# I2CPANEL.net
KiCad netlist of a schematic drawn in EAGLE
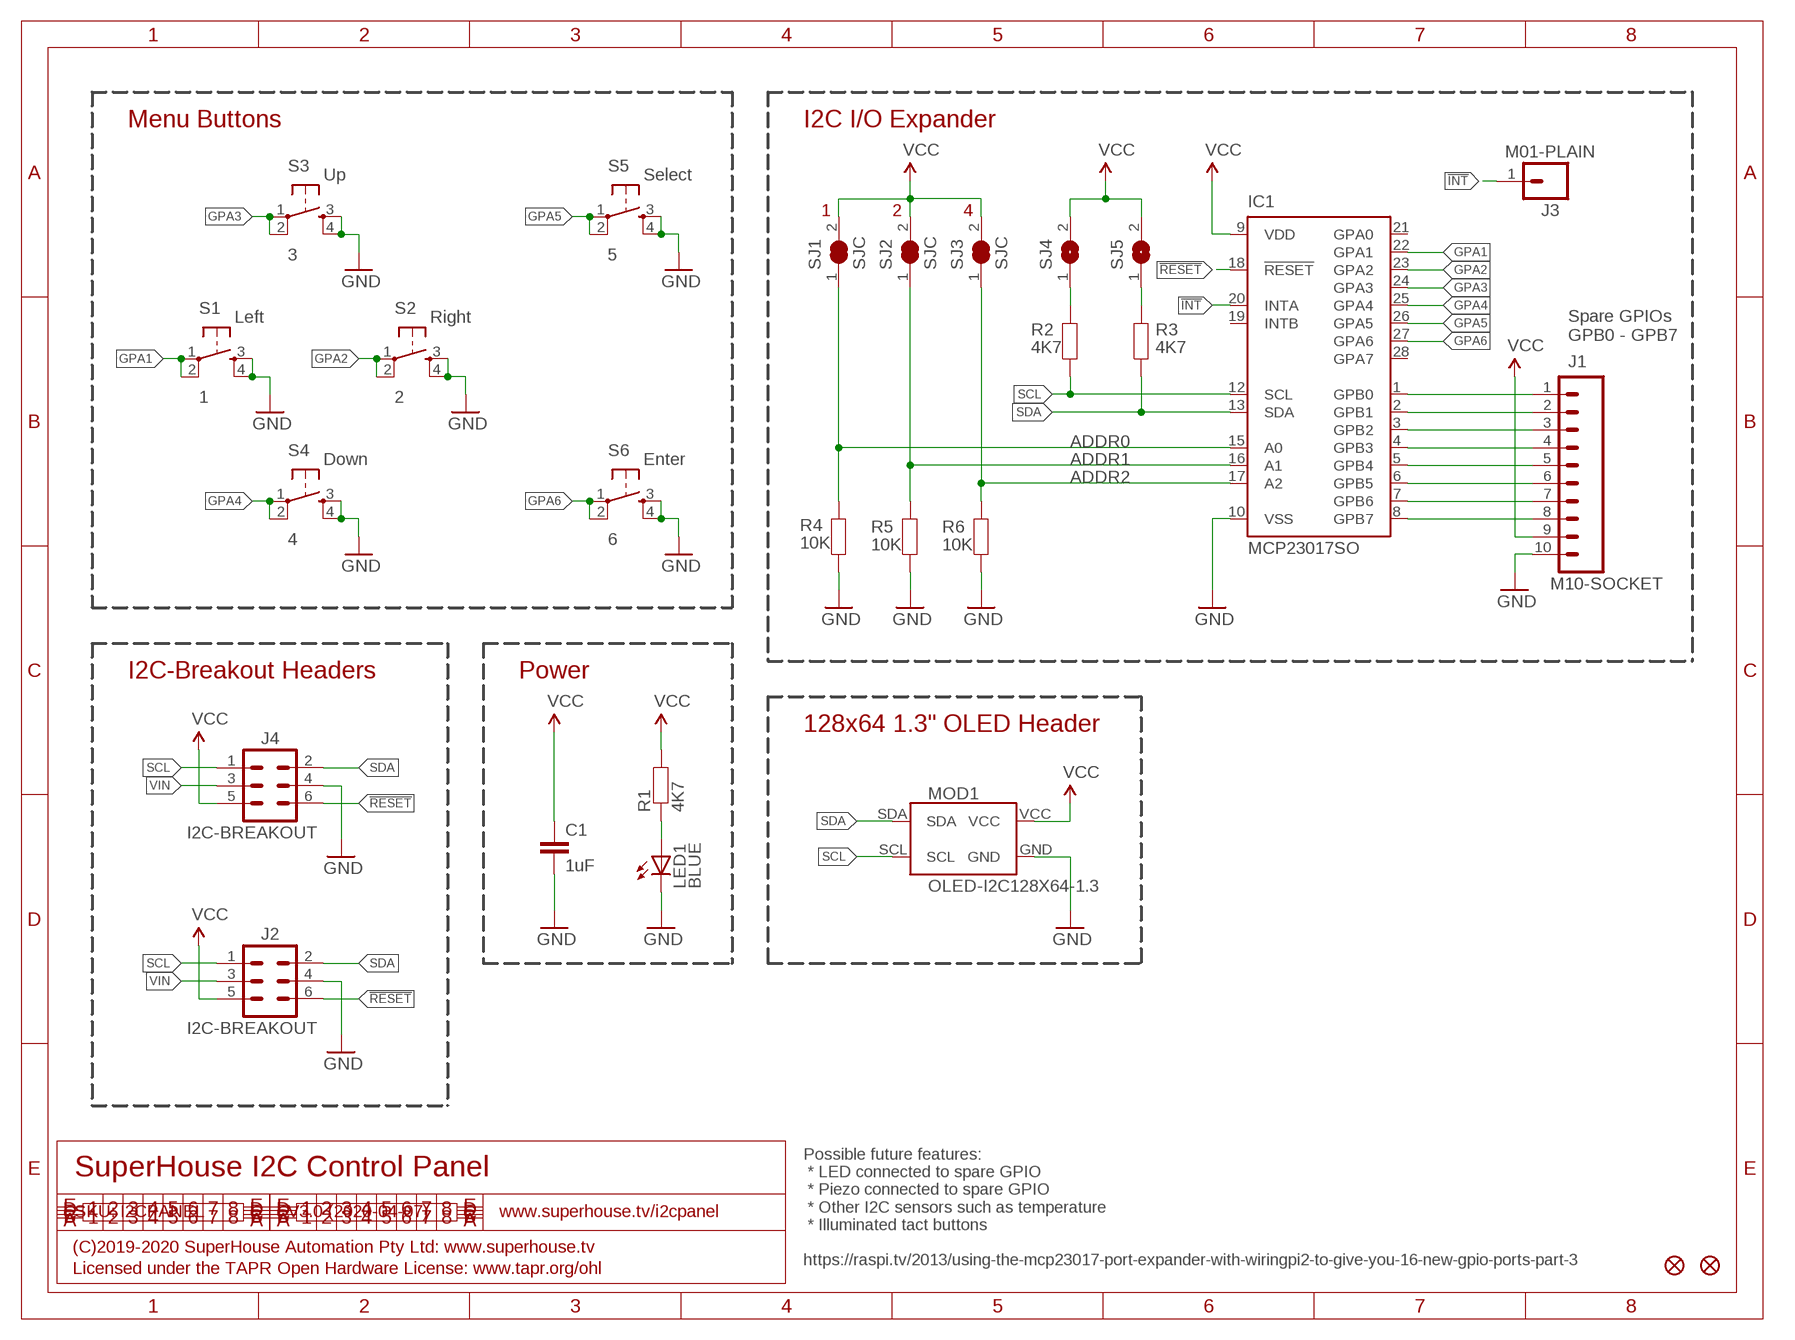
[diagram p0: schematic, sheet 1]

(export (version "E")
  (design (tool "Eeschema 10.0.6"))
  (components
    (comp (ref "C1")
      (value "1uF")
      (footprint "eagle-import:C0603")
      (libsource (lib "eagle-import") (part "CAP0603"))
    )
    (comp (ref "FID1")
      (value "FIDUCIAL1X2.5")
      (footprint "eagle-import:FIDUCIAL-1X2.5")
      (libsource (lib "eagle-import") (part "FIDUCIAL1X2.5"))
    )
    (comp (ref "FID2")
      (value "FIDUCIAL1X2.5")
      (footprint "eagle-import:FIDUCIAL-1X2.5")
      (libsource (lib "eagle-import") (part "FIDUCIAL1X2.5"))
    )
    (comp (ref "IC1")
      (value "MCP23017SO")
      (footprint "eagle-import:SO28W")
      (libsource (lib "eagle-import") (part "MCP23017SO"))
    )
    (comp (ref "J1")
      (value "M10-SOCKET")
      (footprint "eagle-import:1X10-S")
      (libsource (lib "eagle-import") (part "M10-SOCKET"))
    )
    (comp (ref "J2")
      (value "I2C-BREAKOUT")
      (footprint "eagle-import:2X03-SHROUDED")
      (libsource (lib "eagle-import") (part "M02X3-SHROUDED"))
    )
    (comp (ref "J3")
      (value "M01-PLAIN")
      (footprint "eagle-import:1X01")
      (libsource (lib "eagle-import") (part "M01-PLAIN"))
    )
    (comp (ref "J4")
      (value "I2C-BREAKOUT")
      (footprint "eagle-import:2X03-SHROUDED")
      (libsource (lib "eagle-import") (part "M02X3-SHROUDED"))
    )
    (comp (ref "LED1")
      (value "BLUE")
      (footprint "eagle-import:LED-0603")
      (libsource (lib "eagle-import") (part "LED0603"))
    )
    (comp (ref "MOD1")
      (value "OLED-I2C128X64-1.3")
      (footprint "eagle-import:OLED-128X64-1.3")
      (libsource (lib "eagle-import") (part "OLED-I2C128X64-1.3"))
    )
    (comp (ref "R1")
      (value "4K7")
      (footprint "eagle-import:R0603")
      (libsource (lib "eagle-import") (part "RESISTOR0603"))
    )
    (comp (ref "R2")
      (value "4K7")
      (footprint "eagle-import:R0603")
      (libsource (lib "eagle-import") (part "RESISTOR0603"))
    )
    (comp (ref "R3")
      (value "4K7")
      (footprint "eagle-import:R0603")
      (libsource (lib "eagle-import") (part "RESISTOR0603"))
    )
    (comp (ref "R4")
      (value "10K")
      (footprint "eagle-import:R0603")
      (libsource (lib "eagle-import") (part "RESISTOR0603"))
    )
    (comp (ref "R5")
      (value "10K")
      (footprint "eagle-import:R0603")
      (libsource (lib "eagle-import") (part "RESISTOR0603"))
    )
    (comp (ref "R6")
      (value "10K")
      (footprint "eagle-import:R0603")
      (libsource (lib "eagle-import") (part "RESISTOR0603"))
    )
    (comp (ref "S1")
      (value "1")
      (footprint "eagle-import:TACTILE-PTH-6MM")
      (libsource (lib "eagle-import") (part "TAC_SWITCH-PTH-6"))
    )
    (comp (ref "S2")
      (value "2")
      (footprint "eagle-import:TACTILE-PTH-6MM")
      (libsource (lib "eagle-import") (part "TAC_SWITCH-PTH-6"))
    )
    (comp (ref "S3")
      (value "3")
      (footprint "eagle-import:TACTILE-PTH-6MM")
      (libsource (lib "eagle-import") (part "TAC_SWITCH-PTH-6"))
    )
    (comp (ref "S4")
      (value "4")
      (footprint "eagle-import:TACTILE-PTH-6MM")
      (libsource (lib "eagle-import") (part "TAC_SWITCH-PTH-6"))
    )
    (comp (ref "S5")
      (value "5")
      (footprint "eagle-import:TACTILE-PTH-6MM")
      (libsource (lib "eagle-import") (part "TAC_SWITCH-PTH-6"))
    )
    (comp (ref "S6")
      (value "6")
      (footprint "eagle-import:TACTILE-PTH-6MM")
      (libsource (lib "eagle-import") (part "TAC_SWITCH-PTH-6"))
    )
    (comp (ref "SJ1")
      (value "SJC")
      (footprint "eagle-import:SJC")
      (libsource (lib "eagle-import") (part "SJC-NORMAL"))
    )
    (comp (ref "SJ2")
      (value "SJC")
      (footprint "eagle-import:SJC")
      (libsource (lib "eagle-import") (part "SJC-NORMAL"))
    )
    (comp (ref "SJ3")
      (value "SJC")
      (footprint "eagle-import:SJC")
      (libsource (lib "eagle-import") (part "SJC-NORMAL"))
    )
    (comp (ref "SJ4")
      (value "SJN")
      (footprint "eagle-import:SJ")
      (libsource (lib "eagle-import") (part "SJN"))
    )
    (comp (ref "SJ5")
      (value "SJN")
      (footprint "eagle-import:SJ")
      (libsource (lib "eagle-import") (part "SJN"))
    )
  )
  (nets
    (net (code "1") (name "/ADDR0") (class "Default")
      (node (ref "IC1") (pin "15") (pinfunction "A0_15") (pintype "input"))
      (node (ref "R4") (pin "2") (pinfunction "2_2") (pintype "passive"))
      (node (ref "SJ1") (pin "1") (pinfunction "1_1") (pintype "passive"))
    )
    (net (code "2") (name "/ADDR1") (class "Default")
      (node (ref "IC1") (pin "16") (pinfunction "A1_16") (pintype "input"))
      (node (ref "R5") (pin "2") (pinfunction "2_2") (pintype "passive"))
      (node (ref "SJ2") (pin "1") (pinfunction "1_1") (pintype "passive"))
    )
    (net (code "3") (name "/ADDR2") (class "Default")
      (node (ref "IC1") (pin "17") (pinfunction "A2_17") (pintype "input"))
      (node (ref "R6") (pin "2") (pinfunction "2_2") (pintype "passive"))
      (node (ref "SJ3") (pin "1") (pinfunction "1_1") (pintype "passive"))
    )
    (net (code "4") (name "/~{INT}") (class "Default")
      (node (ref "IC1") (pin "20") (pinfunction "INTA_20") (pintype "output"))
      (node (ref "J3") (pin "1") (pinfunction "1_1") (pintype "passive"))
    )
    (net (code "5") (name "/~{RESET}") (class "Default")
      (node (ref "IC1") (pin "18") (pinfunction "~{RESET}_18") (pintype "input"))
      (node (ref "J2") (pin "6") (pinfunction "6_6") (pintype "passive"))
      (node (ref "J4") (pin "6") (pinfunction "6_6") (pintype "passive"))
    )
    (net (code "6") (name "GND") (class "Default")
      (node (ref "C1") (pin "2") (pinfunction "2_2") (pintype "passive"))
      (node (ref "IC1") (pin "10") (pinfunction "VSS_10") (pintype "power_in"))
      (node (ref "J1") (pin "10") (pinfunction "10_10") (pintype "passive"))
      (node (ref "J2") (pin "4") (pinfunction "4_4") (pintype "passive"))
      (node (ref "J4") (pin "4") (pinfunction "4_4") (pintype "passive"))
      (node (ref "LED1") (pin "C") (pinfunction "C_C") (pintype "passive"))
      (node (ref "MOD1") (pin "GND") (pinfunction "GND_GND") (pintype "bidirectional"))
      (node (ref "R4") (pin "1") (pinfunction "1_1") (pintype "passive"))
      (node (ref "R5") (pin "1") (pinfunction "1_1") (pintype "passive"))
      (node (ref "R6") (pin "1") (pinfunction "1_1") (pintype "passive"))
      (node (ref "S1") (pin "3") (pinfunction "3_3") (pintype "passive"))
      (node (ref "S1") (pin "4") (pinfunction "4_4") (pintype "passive"))
      (node (ref "S2") (pin "3") (pinfunction "3_3") (pintype "passive"))
      (node (ref "S2") (pin "4") (pinfunction "4_4") (pintype "passive"))
      (node (ref "S3") (pin "3") (pinfunction "3_3") (pintype "passive"))
      (node (ref "S3") (pin "4") (pinfunction "4_4") (pintype "passive"))
      (node (ref "S4") (pin "3") (pinfunction "3_3") (pintype "passive"))
      (node (ref "S4") (pin "4") (pinfunction "4_4") (pintype "passive"))
      (node (ref "S5") (pin "3") (pinfunction "3_3") (pintype "passive"))
      (node (ref "S5") (pin "4") (pinfunction "4_4") (pintype "passive"))
      (node (ref "S6") (pin "3") (pinfunction "3_3") (pintype "passive"))
      (node (ref "S6") (pin "4") (pinfunction "4_4") (pintype "passive"))
    )
    (net (code "7") (name "GPA1") (class "Default")
      (node (ref "IC1") (pin "22") (pinfunction "GPA1_22") (pintype "bidirectional"))
      (node (ref "S1") (pin "1") (pinfunction "1_1") (pintype "passive"))
      (node (ref "S1") (pin "2") (pinfunction "2_2") (pintype "passive"))
    )
    (net (code "8") (name "GPA2") (class "Default")
      (node (ref "IC1") (pin "23") (pinfunction "GPA2_23") (pintype "bidirectional"))
      (node (ref "S2") (pin "1") (pinfunction "1_1") (pintype "passive"))
      (node (ref "S2") (pin "2") (pinfunction "2_2") (pintype "passive"))
    )
    (net (code "9") (name "GPA3") (class "Default")
      (node (ref "IC1") (pin "24") (pinfunction "GPA3_24") (pintype "bidirectional"))
      (node (ref "S3") (pin "1") (pinfunction "1_1") (pintype "passive"))
      (node (ref "S3") (pin "2") (pinfunction "2_2") (pintype "passive"))
    )
    (net (code "10") (name "GPA4") (class "Default")
      (node (ref "IC1") (pin "25") (pinfunction "GPA4_25") (pintype "bidirectional"))
      (node (ref "S4") (pin "1") (pinfunction "1_1") (pintype "passive"))
      (node (ref "S4") (pin "2") (pinfunction "2_2") (pintype "passive"))
    )
    (net (code "11") (name "GPA5") (class "Default")
      (node (ref "IC1") (pin "26") (pinfunction "GPA5_26") (pintype "bidirectional"))
      (node (ref "S5") (pin "1") (pinfunction "1_1") (pintype "passive"))
      (node (ref "S5") (pin "2") (pinfunction "2_2") (pintype "passive"))
    )
    (net (code "12") (name "GPA6") (class "Default")
      (node (ref "IC1") (pin "27") (pinfunction "GPA6_27") (pintype "bidirectional"))
      (node (ref "S6") (pin "1") (pinfunction "1_1") (pintype "passive"))
      (node (ref "S6") (pin "2") (pinfunction "2_2") (pintype "passive"))
    )
    (net (code "13") (name "Net-(IC1-GPB0)") (class "Default")
      (node (ref "IC1") (pin "1") (pinfunction "GPB0_1") (pintype "bidirectional"))
      (node (ref "J1") (pin "1") (pinfunction "1_1") (pintype "passive"))
    )
    (net (code "14") (name "Net-(IC1-GPB1)") (class "Default")
      (node (ref "IC1") (pin "2") (pinfunction "GPB1_2") (pintype "bidirectional"))
      (node (ref "J1") (pin "2") (pinfunction "2_2") (pintype "passive"))
    )
    (net (code "15") (name "Net-(IC1-GPB2)") (class "Default")
      (node (ref "IC1") (pin "3") (pinfunction "GPB2_3") (pintype "bidirectional"))
      (node (ref "J1") (pin "3") (pinfunction "3_3") (pintype "passive"))
    )
    (net (code "16") (name "Net-(IC1-GPB3)") (class "Default")
      (node (ref "IC1") (pin "4") (pinfunction "GPB3_4") (pintype "bidirectional"))
      (node (ref "J1") (pin "4") (pinfunction "4_4") (pintype "passive"))
    )
    (net (code "17") (name "Net-(IC1-GPB4)") (class "Default")
      (node (ref "IC1") (pin "5") (pinfunction "GPB4_5") (pintype "bidirectional"))
      (node (ref "J1") (pin "5") (pinfunction "5_5") (pintype "passive"))
    )
    (net (code "18") (name "Net-(IC1-GPB5)") (class "Default")
      (node (ref "IC1") (pin "6") (pinfunction "GPB5_6") (pintype "bidirectional"))
      (node (ref "J1") (pin "6") (pinfunction "6_6") (pintype "passive"))
    )
    (net (code "19") (name "Net-(IC1-GPB6)") (class "Default")
      (node (ref "IC1") (pin "7") (pinfunction "GPB6_7") (pintype "bidirectional"))
      (node (ref "J1") (pin "7") (pinfunction "7_7") (pintype "passive"))
    )
    (net (code "20") (name "Net-(IC1-GPB7)") (class "Default")
      (node (ref "IC1") (pin "8") (pinfunction "GPB7_8") (pintype "bidirectional"))
      (node (ref "J1") (pin "8") (pinfunction "8_8") (pintype "passive"))
    )
    (net (code "21") (name "Net-(LED1-PadA)") (class "Default")
      (node (ref "LED1") (pin "A") (pinfunction "A_A") (pintype "passive"))
      (node (ref "R1") (pin "1") (pinfunction "1_1") (pintype "passive"))
    )
    (net (code "22") (name "Net-(R2-Pad2)") (class "Default")
      (node (ref "R2") (pin "2") (pinfunction "2_2") (pintype "passive"))
      (node (ref "SJ4") (pin "1") (pinfunction "1_1") (pintype "passive"))
    )
    (net (code "23") (name "Net-(R3-Pad2)") (class "Default")
      (node (ref "R3") (pin "2") (pinfunction "2_2") (pintype "passive"))
      (node (ref "SJ5") (pin "1") (pinfunction "1_1") (pintype "passive"))
    )
    (net (code "24") (name "SCL") (class "Default")
      (node (ref "IC1") (pin "12") (pinfunction "SCL_12") (pintype "input"))
      (node (ref "J2") (pin "1") (pinfunction "1_1") (pintype "passive"))
      (node (ref "J4") (pin "1") (pinfunction "1_1") (pintype "passive"))
      (node (ref "MOD1") (pin "SCL") (pinfunction "SCL_SCL") (pintype "bidirectional"))
      (node (ref "R2") (pin "1") (pinfunction "1_1") (pintype "passive"))
    )
    (net (code "25") (name "SDA") (class "Default")
      (node (ref "IC1") (pin "13") (pinfunction "SDA_13") (pintype "bidirectional"))
      (node (ref "J2") (pin "2") (pinfunction "2_2") (pintype "passive"))
      (node (ref "J4") (pin "2") (pinfunction "2_2") (pintype "passive"))
      (node (ref "MOD1") (pin "SDA") (pinfunction "SDA_SDA") (pintype "bidirectional"))
      (node (ref "R3") (pin "1") (pinfunction "1_1") (pintype "passive"))
    )
    (net (code "26") (name "VCC") (class "Default")
      (node (ref "C1") (pin "1") (pinfunction "1_1") (pintype "passive"))
      (node (ref "IC1") (pin "9") (pinfunction "VDD_9") (pintype "power_in"))
      (node (ref "J1") (pin "9") (pinfunction "9_9") (pintype "passive"))
      (node (ref "J2") (pin "5") (pinfunction "5_5") (pintype "passive"))
      (node (ref "J4") (pin "5") (pinfunction "5_5") (pintype "passive"))
      (node (ref "MOD1") (pin "VCC") (pinfunction "VCC_VCC") (pintype "bidirectional"))
      (node (ref "R1") (pin "2") (pinfunction "2_2") (pintype "passive"))
      (node (ref "SJ1") (pin "2") (pinfunction "2_2") (pintype "passive"))
      (node (ref "SJ2") (pin "2") (pinfunction "2_2") (pintype "passive"))
      (node (ref "SJ3") (pin "2") (pinfunction "2_2") (pintype "passive"))
      (node (ref "SJ4") (pin "2") (pinfunction "2_2") (pintype "passive"))
      (node (ref "SJ5") (pin "2") (pinfunction "2_2") (pintype "passive"))
    )
    (net (code "27") (name "VIN") (class "Default")
      (node (ref "J2") (pin "3") (pinfunction "3_3") (pintype "passive"))
      (node (ref "J4") (pin "3") (pinfunction "3_3") (pintype "passive"))
    )
    (net (code "28") (name "unconnected-(IC1-GPA0-Pad21)") (class "Default")
      (node (ref "IC1") (pin "21") (pinfunction "GPA0_21") (pintype "bidirectional"))
    )
    (net (code "29") (name "unconnected-(IC1-GPA7-Pad28)") (class "Default")
      (node (ref "IC1") (pin "28") (pinfunction "GPA7_28") (pintype "bidirectional"))
    )
    (net (code "30") (name "unconnected-(IC1-INTB-Pad19)") (class "Default")
      (node (ref "IC1") (pin "19") (pinfunction "INTB_19") (pintype "output"))
    )
  )
)
